# fuse_old.net
KiCad netlist of a schematic drawn in Altium Designer
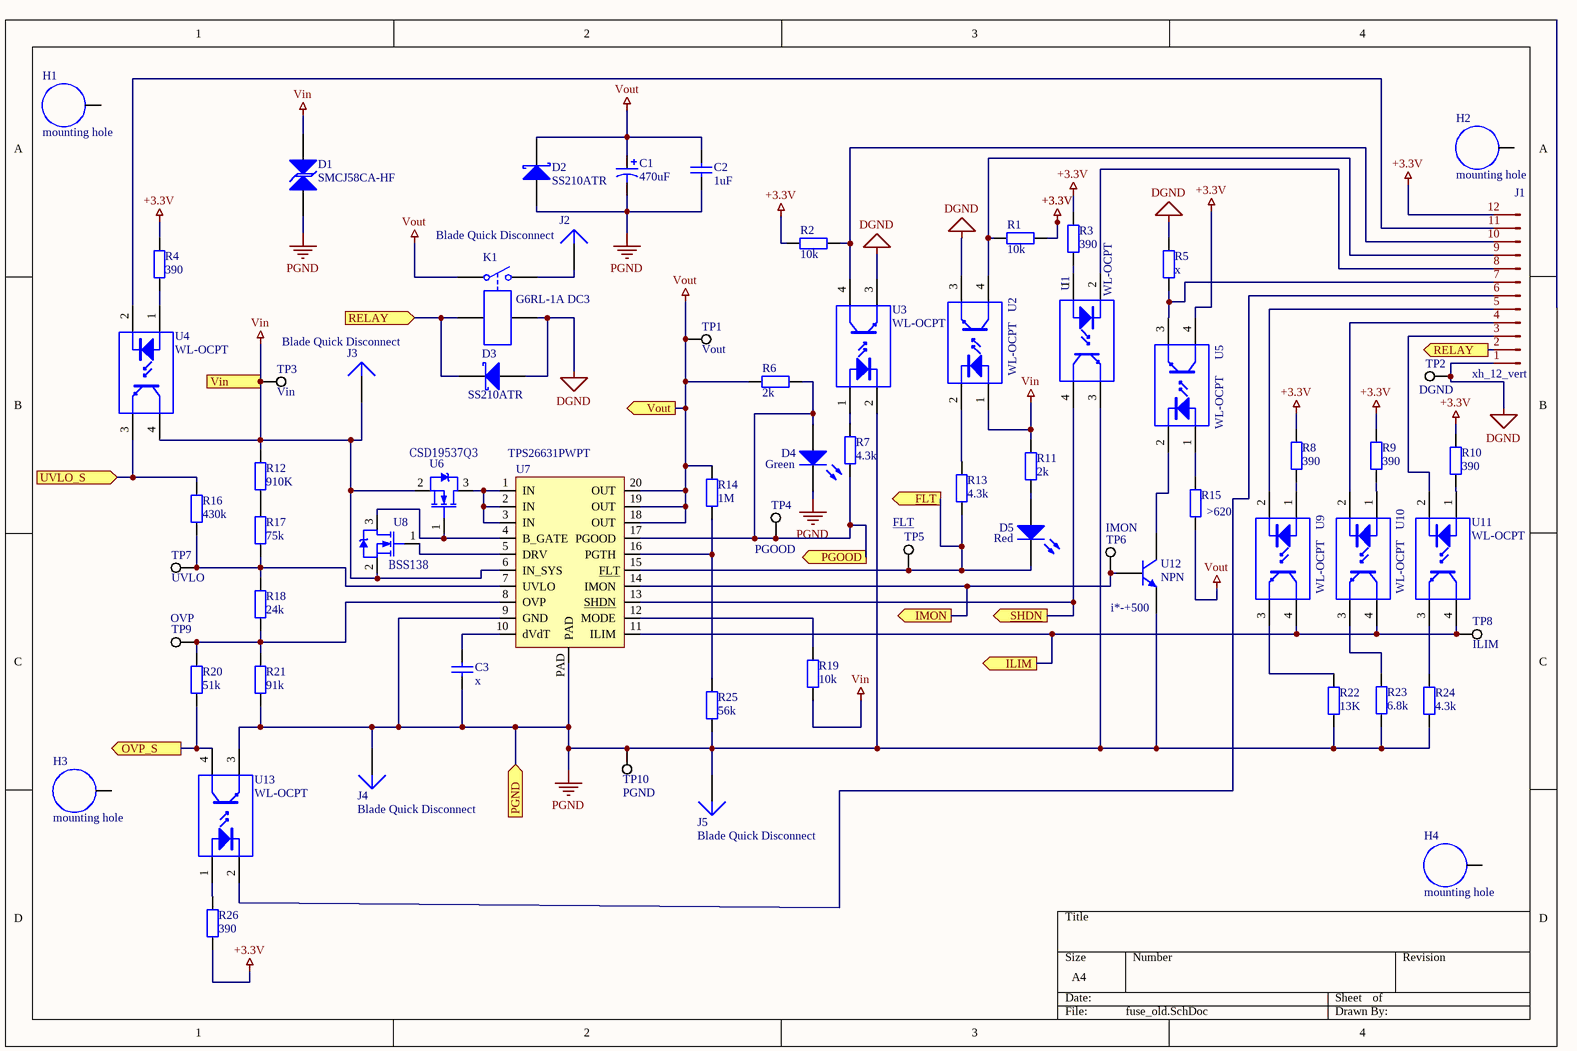
[diagram p0: fuse_old.SchDoc]

(export (version "E")
  (design (tool "Eeschema 10.0.6"))
  (components
    (comp (ref "C1")
      (value "470uF")
      (footprint "8mm smd cap")
      (libsource (lib "generic_components") (part "cap pol"))
    )
    (comp (ref "C2") (value "1uF") (footprint "0805") (libsource (lib "generic_components") (part "cap")))
    (comp (ref "C3") (value "x") (footprint "0805") (libsource (lib "generic_components") (part "cap")))
    (comp (ref "D1")
      (value "SMCJ58CA-HF")
      (footprint "DO-214AB-SMC Bipolar")
      (libsource (lib "generic_components") (part "TVS Diode"))
    )
    (comp (ref "D2")
      (value "SS210ATR")
      (footprint "DO-214AC, SMA")
      (libsource (lib "generic_components") (part "shotkey diode"))
    )
    (comp (ref "D3")
      (value "SS210ATR")
      (footprint "DO-214AC, SMA")
      (libsource (lib "generic_components") (part "shotkey diode"))
    )
    (comp (ref "D4")
      (value "Green")
      (footprint "0805 LED")
      (libsource (lib "generic_components") (part "LED"))
    )
    (comp (ref "D5") (value "Red") (footprint "0805 LED") (libsource (lib "generic_components") (part "LED")))
    (comp (ref "H1")
      (value "mounting hole")
      (footprint "M3 HOLE iso")
      (libsource (lib "generic_components") (part "mounting hole"))
    )
    (comp (ref "H2")
      (value "mounting hole")
      (footprint "M3 HOLE iso")
      (libsource (lib "generic_components") (part "mounting hole"))
    )
    (comp (ref "H3")
      (value "mounting hole")
      (footprint "M3 HOLE iso")
      (libsource (lib "generic_components") (part "mounting hole"))
    )
    (comp (ref "H4")
      (value "mounting hole")
      (footprint "M3 HOLE iso")
      (libsource (lib "generic_components") (part "mounting hole"))
    )
    (comp (ref "J1")
      (value "xh_12_vert")
      (footprint "JST_XH_B12B-XH-A_1x12_P2.50mm_Vertical")
      (libsource (lib "JST") (part "xh_12_vert"))
    )
    (comp (ref "J2")
      (value "Blade Quick Disconnect")
      (footprint "TE blade connector")
      (libsource (lib "generic_conn") (part "Blade Quick Disconnect"))
    )
    (comp (ref "J3")
      (value "Blade Quick Disconnect")
      (footprint "TE blade connector")
      (libsource (lib "generic_conn") (part "Blade Quick Disconnect"))
    )
    (comp (ref "J4")
      (value "Blade Quick Disconnect")
      (footprint "TE blade connector")
      (libsource (lib "generic_conn") (part "Blade Quick Disconnect"))
    )
    (comp (ref "J5")
      (value "Blade Quick Disconnect")
      (footprint "TE blade connector")
      (libsource (lib "generic_conn") (part "Blade Quick Disconnect"))
    )
    (comp (ref "K1")
      (value "G6RL-1A DC3")
      (footprint "G6RL-1A DC3 relay")
      (libsource (lib "generic_components") (part "Relay"))
    )
    (comp (ref "R1") (value "10k") (footprint "0805") (libsource (lib "") (part "res0805_3")))
    (comp (ref "R2") (value "10k") (footprint "0805") (libsource (lib "") (part "res0805_2")))
    (comp (ref "R3") (value "390") (footprint "0805") (libsource (lib "generic_components") (part "res0805")))
    (comp (ref "R4") (value "390") (footprint "0805") (libsource (lib "generic_components") (part "res0805")))
    (comp (ref "R5") (value "x") (footprint "0805") (libsource (lib "generic_components") (part "res0805")))
    (comp (ref "R6") (value "2k") (footprint "0805") (libsource (lib "") (part "res0805_3")))
    (comp (ref "R7")
      (value "4.3k")
      (footprint "0805")
      (libsource (lib "generic_components") (part "res0805"))
    )
    (comp (ref "R8") (value "390") (footprint "0805") (libsource (lib "generic_components") (part "res0805")))
    (comp (ref "R9") (value "390") (footprint "0805") (libsource (lib "generic_components") (part "res0805")))
    (comp (ref "R10")
      (value "390")
      (footprint "0805")
      (libsource (lib "generic_components") (part "res0805"))
    )
    (comp (ref "R11") (value "2k") (footprint "0805") (libsource (lib "generic_components") (part "res0805")))
    (comp (ref "R12")
      (value "910K")
      (footprint "0805")
      (libsource (lib "generic_components") (part "res0805"))
    )
    (comp (ref "R13")
      (value "4.3k")
      (footprint "0805")
      (libsource (lib "generic_components") (part "res0805"))
    )
    (comp (ref "R14") (value "1M") (footprint "0805") (libsource (lib "generic_components") (part "res0805")))
    (comp (ref "R15")
      (value ">620")
      (footprint "0805")
      (libsource (lib "generic_components") (part "res0805"))
    )
    (comp (ref "R16")
      (value "430k")
      (footprint "0805")
      (libsource (lib "generic_components") (part "res0805"))
    )
    (comp (ref "R17")
      (value "75k")
      (footprint "0805")
      (libsource (lib "generic_components") (part "res0805"))
    )
    (comp (ref "R18")
      (value "24k")
      (footprint "0805")
      (libsource (lib "generic_components") (part "res0805"))
    )
    (comp (ref "R19")
      (value "10k")
      (footprint "0805")
      (libsource (lib "generic_components") (part "res0805"))
    )
    (comp (ref "R20")
      (value "51k")
      (footprint "0805")
      (libsource (lib "generic_components") (part "res0805"))
    )
    (comp (ref "R21")
      (value "91k")
      (footprint "0805")
      (libsource (lib "generic_components") (part "res0805"))
    )
    (comp (ref "R22")
      (value "13K")
      (footprint "0805")
      (libsource (lib "generic_components") (part "res0805"))
    )
    (comp (ref "R23")
      (value "6.8k")
      (footprint "0805")
      (libsource (lib "generic_components") (part "res0805"))
    )
    (comp (ref "R24")
      (value "4.3k")
      (footprint "0805")
      (libsource (lib "generic_components") (part "res0805"))
    )
    (comp (ref "R25")
      (value "56k")
      (footprint "0805")
      (libsource (lib "generic_components") (part "res0805"))
    )
    (comp (ref "R26") (value "390") (footprint "0805") (libsource (lib "") (part "res0805_1")))
    (comp (ref "TP1")
      (value "Vout")
      (footprint "Test Loop 1.6mm")
      (libsource (lib "generic_components") (part "Test point"))
    )
    (comp (ref "TP2")
      (value "DGND")
      (footprint "Test Loop 1.6mm")
      (libsource (lib "generic_components") (part "Test point"))
    )
    (comp (ref "TP3")
      (value "Vin")
      (footprint "Test Loop 1.6mm")
      (libsource (lib "generic_components") (part "Test point"))
    )
    (comp (ref "TP4")
      (value "PGOOD")
      (footprint "Test Loop 1.6mm")
      (libsource (lib "generic_components") (part "Test point"))
    )
    (comp (ref "TP5")
      (value "FLT")
      (footprint "Test Loop 1.6mm")
      (libsource (lib "generic_components") (part "Test point"))
    )
    (comp (ref "TP6")
      (value "IMON")
      (footprint "Test Loop 1.6mm")
      (libsource (lib "generic_components") (part "Test point"))
    )
    (comp (ref "TP7")
      (value "UVLO")
      (footprint "Test Loop 1.6mm")
      (libsource (lib "generic_components") (part "Test point"))
    )
    (comp (ref "TP8")
      (value "ILIM")
      (footprint "Test Loop 1.6mm")
      (libsource (lib "generic_components") (part "Test point"))
    )
    (comp (ref "TP9")
      (value "OVP")
      (footprint "Test Loop 1.6mm")
      (libsource (lib "generic_components") (part "Test point"))
    )
    (comp (ref "TP10")
      (value "PGND")
      (footprint "Test Loop 1.6mm")
      (libsource (lib "generic_components") (part "Test point"))
    )
    (comp (ref "U1")
      (value "WL-OCPT")
      (footprint "4-SOP_WE_opto-isolator")
      (libsource (lib "generic_components") (part "optoc WE"))
    )
    (comp (ref "U2")
      (value "WL-OCPT")
      (footprint "4-SOP_WE_opto-isolator")
      (libsource (lib "generic_components") (part "optoc WE"))
    )
    (comp (ref "U3")
      (value "WL-OCPT")
      (footprint "4-SOP_WE_opto-isolator")
      (libsource (lib "generic_components") (part "optoc WE"))
    )
    (comp (ref "U4")
      (value "WL-OCPT")
      (footprint "4-SOP_WE_opto-isolator")
      (libsource (lib "generic_components") (part "optoc WE"))
    )
    (comp (ref "U5")
      (value "WL-OCPT")
      (footprint "4-SOP_WE_opto-isolator")
      (libsource (lib "generic_components") (part "optoc WE"))
    )
    (comp (ref "U6")
      (value "‎CSD19537Q3‎")
      (footprint "8-VSON (3,3x3,3)")
      (libsource (lib "generic_components") (part "N-mosfet en"))
    )
    (comp (ref "U7")
      (value "TPS26631PWPT")
      (footprint "TSSOP_P065S6.6x6.6")
      (libsource (lib "ti") (part "TPS26631PWPT"))
    )
    (comp (ref "U8")
      (value "BSS138‎")
      (footprint "SOT-23-3")
      (libsource (lib "generic_components") (part "N-mosfet en"))
    )
    (comp (ref "U9")
      (value "WL-OCPT")
      (footprint "4-SOP_WE_opto-isolator")
      (libsource (lib "generic_components") (part "optoc WE"))
    )
    (comp (ref "U10")
      (value "WL-OCPT")
      (footprint "4-SOP_WE_opto-isolator")
      (libsource (lib "generic_components") (part "optoc WE"))
    )
    (comp (ref "U11")
      (value "WL-OCPT")
      (footprint "4-SOP_WE_opto-isolator")
      (libsource (lib "generic_components") (part "optoc WE"))
    )
    (comp (ref "U12")
      (value "NPN")
      (footprint "SOT23(TO-236AB)P095S230x290")
      (libsource (lib "generic_components") (part "NPN"))
    )
    (comp (ref "U13")
      (value "WL-OCPT")
      (footprint "4-SOP_WE_opto-isolator")
      (libsource (lib "generic_components") (part "optoc WE"))
    )
  )
  (nets
    (net (code "1") (name "+3.3V") (class "Default")
      (node (ref "J1") (pin "12") (pinfunction "Pin_11_12") (pintype "passive"))
      (node (ref "R1") (pin "1") (pintype "passive"))
      (node (ref "R10") (pin "2") (pinfunction "2_2") (pintype "passive"))
      (node (ref "R2") (pin "1") (pintype "passive"))
      (node (ref "R26") (pin "2") (pinfunction "2_2") (pintype "passive"))
      (node (ref "R3") (pin "2") (pinfunction "2_2") (pintype "passive"))
      (node (ref "R4") (pin "2") (pinfunction "2_2") (pintype "passive"))
      (node (ref "R8") (pin "2") (pinfunction "2_2") (pintype "passive"))
      (node (ref "R9") (pin "2") (pinfunction "2_2") (pintype "passive"))
      (node (ref "U5") (pin "4") (pinfunction "C_4") (pintype "passive"))
    )
    (net (code "2") (name "/FLT") (class "Default")
      (node (ref "D5") (pin "2") (pinfunction "K_2") (pintype "passive"))
      (node (ref "R13") (pin "1") (pintype "passive"))
      (node (ref "TP5") (pin "1") (pintype "passive"))
      (node (ref "U7") (pin "15") (pinfunction "FLT_15") (pintype "passive"))
    )
    (net (code "3") (name "/ILIM") (class "Default")
      (node (ref "TP8") (pin "1") (pintype "passive"))
      (node (ref "U10") (pin "4") (pinfunction "C_4") (pintype "passive"))
      (node (ref "U11") (pin "4") (pinfunction "C_4") (pintype "passive"))
      (node (ref "U7") (pin "11") (pinfunction "ILIM_11") (pintype "passive"))
      (node (ref "U9") (pin "4") (pinfunction "C_4") (pintype "passive"))
    )
    (net (code "4") (name "/IMON") (class "Default")
      (node (ref "TP6") (pin "1") (pintype "passive"))
      (node (ref "U12") (pin "1") (pinfunction "B_1") (pintype "passive"))
      (node (ref "U7") (pin "14") (pinfunction "IMON_14") (pintype "passive"))
    )
    (net (code "5") (name "/OVP_S") (class "Default")
      (node (ref "R20") (pin "1") (pintype "passive"))
      (node (ref "U13") (pin "4") (pinfunction "C_4") (pintype "passive"))
    )
    (net (code "6") (name "/PGOOD") (class "Default")
      (node (ref "D4") (pin "1") (pinfunction "A_1") (pintype "passive"))
      (node (ref "R6") (pin "1") (pintype "passive"))
      (node (ref "R7") (pin "1") (pintype "passive"))
      (node (ref "TP4") (pin "1") (pintype "passive"))
      (node (ref "U7") (pin "17") (pinfunction "PGOOD_17") (pintype "passive"))
    )
    (net (code "7") (name "/RELAY") (class "Default")
      (node (ref "D3") (pin "2") (pinfunction "K_2") (pintype "passive"))
      (node (ref "J1") (pin "2") (pinfunction "Pin_2_2") (pintype "passive"))
      (node (ref "K1") (pin "1") (pinfunction "1_1") (pintype "passive"))
    )
    (net (code "8") (name "/SHDN") (class "Default")
      (node (ref "U1") (pin "4") (pinfunction "C_4") (pintype "passive"))
      (node (ref "U7") (pin "13") (pinfunction "SHDN_13") (pintype "passive"))
    )
    (net (code "9") (name "/UVLO_S") (class "Default")
      (node (ref "R16") (pin "2") (pinfunction "2_2") (pintype "passive"))
      (node (ref "U4") (pin "3") (pinfunction "E_3") (pintype "passive"))
    )
    (net (code "10") (name "DGND") (class "Default")
      (node (ref "D3") (pin "1") (pinfunction "A_1") (pintype "passive"))
      (node (ref "J1") (pin "1") (pinfunction "Pin_1_1") (pintype "passive"))
      (node (ref "K1") (pin "5") (pinfunction "5_5") (pintype "passive"))
      (node (ref "R5") (pin "2") (pinfunction "2_2") (pintype "passive"))
      (node (ref "TP2") (pin "1") (pintype "passive"))
      (node (ref "U2") (pin "3") (pinfunction "E_3") (pintype "passive"))
      (node (ref "U3") (pin "3") (pinfunction "E_3") (pintype "passive"))
    )
    (net (code "11") (name "Net-(D5-A)") (class "Default")
      (node (ref "D5") (pin "1") (pinfunction "A_1") (pintype "passive"))
      (node (ref "R11") (pin "1") (pintype "passive"))
    )
    (net (code "12") (name "Net-(J1-Pin_3)") (class "Default")
      (node (ref "J1") (pin "3") (pinfunction "Pin_3_3") (pintype "passive"))
      (node (ref "U11") (pin "2") (pinfunction "C_2") (pintype "passive"))
    )
    (net (code "13") (name "Net-(J1-Pin_4)") (class "Default")
      (node (ref "J1") (pin "4") (pinfunction "Pin_4_4") (pintype "passive"))
      (node (ref "U10") (pin "2") (pinfunction "C_2") (pintype "passive"))
    )
    (net (code "14") (name "Net-(J1-Pin_5)") (class "Default")
      (node (ref "J1") (pin "5") (pinfunction "Pin_5_5") (pintype "passive"))
      (node (ref "U9") (pin "2") (pinfunction "C_2") (pintype "passive"))
    )
    (net (code "15") (name "Net-(J1-Pin_6)") (class "Default")
      (node (ref "J1") (pin "6") (pinfunction "Pin_6_6") (pintype "passive"))
      (node (ref "U13") (pin "2") (pinfunction "C_2") (pintype "passive"))
    )
    (net (code "16") (name "Net-(J1-Pin_7)") (class "Default")
      (node (ref "J1") (pin "7") (pinfunction "Pin_7_7") (pintype "passive"))
      (node (ref "R5") (pin "1") (pintype "passive"))
      (node (ref "U5") (pin "3") (pinfunction "E_3") (pintype "passive"))
    )
    (net (code "17") (name "Net-(J1-Pin_8)") (class "Default")
      (node (ref "J1") (pin "8") (pinfunction "Pin_8_8") (pintype "passive"))
      (node (ref "U1") (pin "2") (pinfunction "C_2") (pintype "passive"))
    )
    (net (code "18") (name "Net-(J1-Pin_9)") (class "Default")
      (node (ref "J1") (pin "9") (pinfunction "Pin_9_9") (pintype "passive"))
      (node (ref "R1") (pin "2") (pinfunction "2_2") (pintype "passive"))
      (node (ref "U2") (pin "4") (pinfunction "C_4") (pintype "passive"))
    )
    (net (code "19") (name "Net-(J1-Pin_10)") (class "Default")
      (node (ref "J1") (pin "10") (pinfunction "Pin_10_10") (pintype "passive"))
      (node (ref "R2") (pin "2") (pinfunction "2_2") (pintype "passive"))
      (node (ref "U3") (pin "4") (pinfunction "C_4") (pintype "passive"))
    )
    (net (code "20") (name "Net-(J1-Pin_11-Pad11)") (class "Default")
      (node (ref "J1") (pin "11") (pinfunction "Pin_11_11") (pintype "passive"))
      (node (ref "U4") (pin "2") (pinfunction "C_2") (pintype "passive"))
    )
    (net (code "21") (name "Net-(J2-Pad1)") (class "Default")
      (node (ref "J2") (pin "1") (pinfunction "1_1") (pintype "passive"))
      (node (ref "K1") (pin "3") (pinfunction "3_3") (pintype "passive"))
    )
    (net (code "22") (name "Net-(R12-Pad1)") (class "Default")
      (node (ref "R12") (pin "1") (pintype "passive"))
      (node (ref "R17") (pin "2") (pinfunction "2_2") (pintype "passive"))
    )
    (net (code "23") (name "Net-(R13-Pad2)") (class "Default")
      (node (ref "R13") (pin "2") (pinfunction "2_2") (pintype "passive"))
      (node (ref "U2") (pin "2") (pinfunction "C_2") (pintype "passive"))
    )
    (net (code "24") (name "Net-(U1-A)") (class "Default")
      (node (ref "R3") (pin "1") (pintype "passive"))
      (node (ref "U1") (pin "1") (pinfunction "A_1") (pintype "passive"))
    )
    (net (code "25") (name "Net-(U3-A)") (class "Default")
      (node (ref "R7") (pin "2") (pinfunction "2_2") (pintype "passive"))
      (node (ref "U3") (pin "1") (pinfunction "A_1") (pintype "passive"))
    )
    (net (code "26") (name "Net-(U4-A)") (class "Default")
      (node (ref "R4") (pin "1") (pintype "passive"))
      (node (ref "U4") (pin "1") (pinfunction "A_1") (pintype "passive"))
    )
    (net (code "27") (name "Net-(U5-A)") (class "Default")
      (node (ref "R15") (pin "2") (pinfunction "2_2") (pintype "passive"))
      (node (ref "U5") (pin "1") (pinfunction "A_1") (pintype "passive"))
    )
    (net (code "28") (name "Net-(U6-G)") (class "Default")
      (node (ref "U6") (pin "1") (pinfunction "G_1") (pintype "passive"))
      (node (ref "U7") (pin "4") (pinfunction "B_GATE_4") (pintype "passive"))
      (node (ref "U8") (pin "3") (pinfunction "S_3") (pintype "passive"))
    )
    (net (code "29") (name "Net-(U6-S)") (class "Default")
      (node (ref "U6") (pin "3") (pinfunction "S_3") (pintype "passive"))
      (node (ref "U7") (pin "1") (pinfunction "IN_1") (pintype "passive"))
      (node (ref "U7") (pin "2") (pinfunction "IN_2") (pintype "passive"))
      (node (ref "U7") (pin "3") (pinfunction "IN_3") (pintype "passive"))
    )
    (net (code "30") (name "Net-(U7-DRV)") (class "Default")
      (node (ref "U7") (pin "5") (pinfunction "DRV_5") (pintype "passive"))
      (node (ref "U8") (pin "1") (pinfunction "G_1") (pintype "passive"))
    )
    (net (code "31") (name "Net-(U7-MODE)") (class "Default")
      (node (ref "R19") (pin "2") (pinfunction "2_2") (pintype "passive"))
      (node (ref "U7") (pin "12") (pinfunction "MODE_12") (pintype "passive"))
    )
    (net (code "32") (name "Net-(U7-OVP)") (class "Default")
      (node (ref "R18") (pin "1") (pintype "passive"))
      (node (ref "R20") (pin "2") (pinfunction "2_2") (pintype "passive"))
      (node (ref "R21") (pin "2") (pinfunction "2_2") (pintype "passive"))
      (node (ref "TP9") (pin "1") (pintype "passive"))
      (node (ref "U7") (pin "8") (pinfunction "OVP_8") (pintype "passive"))
    )
    (net (code "33") (name "Net-(U7-PGTH)") (class "Default")
      (node (ref "R14") (pin "1") (pintype "passive"))
      (node (ref "R25") (pin "2") (pinfunction "2_2") (pintype "passive"))
      (node (ref "U7") (pin "16") (pinfunction "PGTH_16") (pintype "passive"))
    )
    (net (code "34") (name "Net-(U7-UVLO)") (class "Default")
      (node (ref "R16") (pin "1") (pintype "passive"))
      (node (ref "R17") (pin "1") (pintype "passive"))
      (node (ref "R18") (pin "2") (pinfunction "2_2") (pintype "passive"))
      (node (ref "TP7") (pin "1") (pintype "passive"))
      (node (ref "U7") (pin "7") (pinfunction "UVLO_7") (pintype "passive"))
    )
    (net (code "35") (name "Net-(U7-dVdT)") (class "Default")
      (node (ref "C3") (pin "1") (pinfunction "1_1") (pintype "passive"))
      (node (ref "U7") (pin "10") (pinfunction "dVdT_10") (pintype "passive"))
    )
    (net (code "36") (name "Net-(U9-A)") (class "Default")
      (node (ref "R8") (pin "1") (pintype "passive"))
      (node (ref "U9") (pin "1") (pinfunction "A_1") (pintype "passive"))
    )
    (net (code "37") (name "Net-(U9-E)") (class "Default")
      (node (ref "R22") (pin "2") (pinfunction "2_2") (pintype "passive"))
      (node (ref "U9") (pin "3") (pinfunction "E_3") (pintype "passive"))
    )
    (net (code "38") (name "Net-(U10-A)") (class "Default")
      (node (ref "R9") (pin "1") (pintype "passive"))
      (node (ref "U10") (pin "1") (pinfunction "A_1") (pintype "passive"))
    )
    (net (code "39") (name "Net-(U10-E)") (class "Default")
      (node (ref "R23") (pin "2") (pinfunction "2_2") (pintype "passive"))
      (node (ref "U10") (pin "3") (pinfunction "E_3") (pintype "passive"))
    )
    (net (code "40") (name "Net-(U11-A)") (class "Default")
      (node (ref "R10") (pin "1") (pintype "passive"))
      (node (ref "U11") (pin "1") (pinfunction "A_1") (pintype "passive"))
    )
    (net (code "41") (name "Net-(U11-E)") (class "Default")
      (node (ref "R24") (pin "2") (pinfunction "2_2") (pintype "passive"))
      (node (ref "U11") (pin "3") (pinfunction "E_3") (pintype "passive"))
    )
    (net (code "42") (name "Net-(U12-C)") (class "Default")
      (node (ref "U12") (pin "3") (pinfunction "C_3") (pintype "passive"))
      (node (ref "U5") (pin "2") (pinfunction "C_2") (pintype "passive"))
    )
    (net (code "43") (name "Net-(U13-A)") (class "Default")
      (node (ref "R26") (pin "1") (pintype "passive"))
      (node (ref "U13") (pin "1") (pinfunction "A_1") (pintype "passive"))
    )
    (net (code "44") (name "PGND") (class "Default")
      (node (ref "C1") (pin "2") (pinfunction "2_2") (pintype "passive"))
      (node (ref "C2") (pin "1") (pinfunction "1_1") (pintype "passive"))
      (node (ref "C3") (pin "2") (pinfunction "2_2") (pintype "passive"))
      (node (ref "D1") (pin "1") (pinfunction "A_1") (pintype "passive"))
      (node (ref "D2") (pin "1") (pinfunction "A_1") (pintype "passive"))
      (node (ref "D4") (pin "2") (pinfunction "K_2") (pintype "passive"))
      (node (ref "J4") (pin "1") (pinfunction "1_1") (pintype "passive"))
      (node (ref "J5") (pin "1") (pinfunction "1_1") (pintype "passive"))
      (node (ref "R21") (pin "1") (pintype "passive"))
      (node (ref "R22") (pin "1") (pintype "passive"))
      (node (ref "R23") (pin "1") (pintype "passive"))
      (node (ref "R24") (pin "1") (pintype "passive"))
      (node (ref "R25") (pin "1") (pintype "passive"))
      (node (ref "TP10") (pin "1") (pintype "passive"))
      (node (ref "U1") (pin "3") (pinfunction "E_3") (pintype "passive"))
      (node (ref "U12") (pin "2") (pinfunction "E_2") (pintype "passive"))
      (node (ref "U13") (pin "3") (pinfunction "E_3") (pintype "passive"))
      (node (ref "U3") (pin "2") (pinfunction "C_2") (pintype "passive"))
      (node (ref "U7") (pin "9") (pinfunction "GND_9") (pintype "passive"))
      (node (ref "U7") (pin "PAD") (pinfunction "PAD_PAD") (pintype "passive"))
    )
    (net (code "45") (name "Vin") (class "Default")
      (node (ref "D1") (pin "2") (pinfunction "K_2") (pintype "passive"))
      (node (ref "J3") (pin "1") (pinfunction "1_1") (pintype "passive"))
      (node (ref "R11") (pin "2") (pinfunction "2_2") (pintype "passive"))
      (node (ref "R12") (pin "2") (pinfunction "2_2") (pintype "passive"))
      (node (ref "R19") (pin "1") (pintype "passive"))
      (node (ref "TP3") (pin "1") (pintype "passive"))
      (node (ref "U2") (pin "1") (pinfunction "A_1") (pintype "passive"))
      (node (ref "U4") (pin "4") (pinfunction "C_4") (pintype "passive"))
      (node (ref "U6") (pin "2") (pinfunction "D_2") (pintype "passive"))
      (node (ref "U7") (pin "6") (pinfunction "IN_SYS_6") (pintype "passive"))
      (node (ref "U8") (pin "2") (pinfunction "D_2") (pintype "passive"))
    )
    (net (code "46") (name "Vout") (class "Default")
      (node (ref "C1") (pin "1") (pinfunction "1_1") (pintype "passive"))
      (node (ref "C2") (pin "2") (pinfunction "2_2") (pintype "passive"))
      (node (ref "D2") (pin "2") (pinfunction "K_2") (pintype "passive"))
      (node (ref "K1") (pin "2") (pinfunction "2_2") (pintype "passive"))
      (node (ref "R14") (pin "2") (pinfunction "2_2") (pintype "passive"))
      (node (ref "R15") (pin "1") (pintype "passive"))
      (node (ref "R6") (pin "2") (pinfunction "2_2") (pintype "passive"))
      (node (ref "TP1") (pin "1") (pintype "passive"))
      (node (ref "U7") (pin "18") (pinfunction "OUT_18") (pintype "passive"))
      (node (ref "U7") (pin "19") (pinfunction "OUT_19") (pintype "passive"))
      (node (ref "U7") (pin "20") (pinfunction "OUT_20") (pintype "passive"))
    )
    (net (code "47") (name "unconnected-(H1-Pad1)") (class "Default")
      (node (ref "H1") (pin "1") (pintype "passive"))
    )
    (net (code "48") (name "unconnected-(H2-Pad1)") (class "Default")
      (node (ref "H2") (pin "1") (pintype "passive"))
    )
    (net (code "49") (name "unconnected-(H3-Pad1)") (class "Default")
      (node (ref "H3") (pin "1") (pintype "passive"))
    )
    (net (code "50") (name "unconnected-(H4-Pad1)") (class "Default")
      (node (ref "H4") (pin "1") (pintype "passive"))
    )
  )
)
